# RFM12B_Breakout.net
KiCad netlist of a schematic drawn in EAGLE
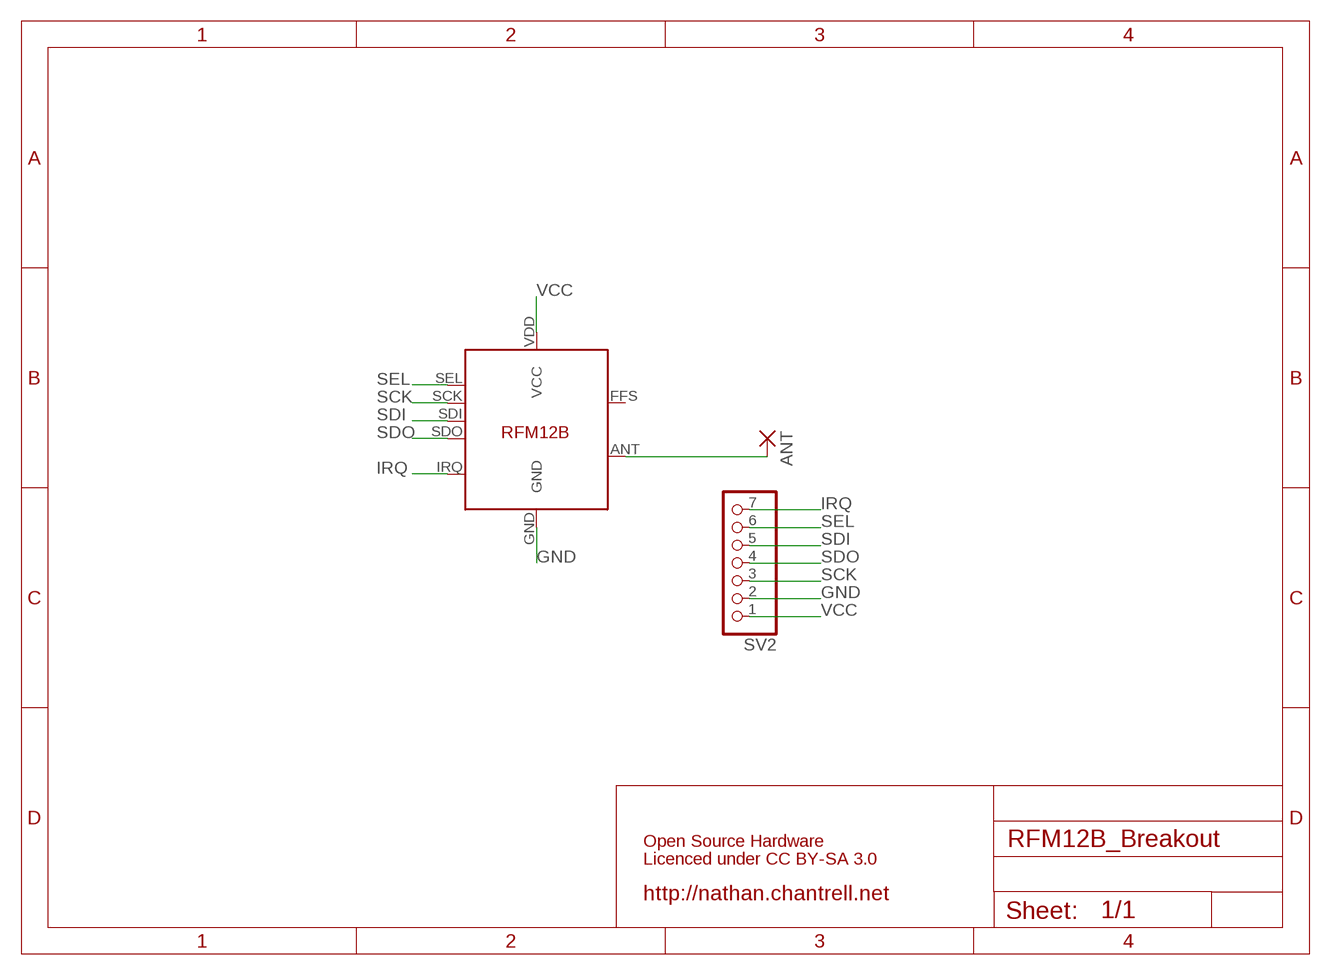
[diagram p0: schematic, sheet 1]

(export (version "E")
  (design (tool "Eeschema 10.0.6"))
  (components
    (comp (ref "ANT")
      (value "1,6/0,8")
      (footprint "eagle-import:1,6_0,8")
      (libsource (lib "eagle-import") (part "1,6/0,8"))
    )
    (comp (ref "SV2")
      (value "PINHD-1X7")
      (footprint "eagle-import:1X07")
      (libsource (lib "eagle-import") (part "PINHD-1X7"))
    )
    (comp (ref "U$1")
      (value "RFM12B")
      (footprint "eagle-import:RFM12B")
      (libsource (lib "eagle-import") (part "RFM12B"))
    )
  )
  (nets
    (net (code "1") (name "/GND") (class "Default")
      (node (ref "SV2") (pin "2") (pinfunction "2_2") (pintype "passive"))
      (node (ref "U$1") (pin "GND") (pinfunction "GND_GND") (pintype "power_in"))
    )
    (net (code "2") (name "/IRQ") (class "Default")
      (node (ref "SV2") (pin "7") (pinfunction "7_7") (pintype "passive"))
      (node (ref "U$1") (pin "IRQ") (pinfunction "IRQ_IRQ") (pintype "open_collector"))
    )
    (net (code "3") (name "/SCK") (class "Default")
      (node (ref "SV2") (pin "3") (pinfunction "3_3") (pintype "passive"))
      (node (ref "U$1") (pin "SCK") (pinfunction "SCK_SCK") (pintype "input"))
    )
    (net (code "4") (name "/SDI") (class "Default")
      (node (ref "SV2") (pin "5") (pinfunction "5_5") (pintype "passive"))
      (node (ref "U$1") (pin "SDI") (pinfunction "SDI_SDI") (pintype "input"))
    )
    (net (code "5") (name "/SDO") (class "Default")
      (node (ref "SV2") (pin "4") (pinfunction "4_4") (pintype "passive"))
      (node (ref "U$1") (pin "SDO") (pinfunction "SDO_SDO") (pintype "output"))
    )
    (net (code "6") (name "/SEL") (class "Default")
      (node (ref "SV2") (pin "6") (pinfunction "6_6") (pintype "passive"))
      (node (ref "U$1") (pin "SEL") (pinfunction "SEL_SEL") (pintype "input"))
    )
    (net (code "7") (name "/VCC") (class "Default")
      (node (ref "SV2") (pin "1") (pinfunction "1_1") (pintype "passive"))
      (node (ref "U$1") (pin "VDD") (pinfunction "VCC_VDD") (pintype "power_in"))
    )
    (net (code "8") (name "Net-(ANT-P)") (class "Default")
      (node (ref "ANT") (pin "1") (pinfunction "P_1") (pintype "passive"))
      (node (ref "U$1") (pin "ANT") (pinfunction "ANT_ANT") (pintype "passive"))
    )
    (net (code "9") (name "unconnected-(U$1-PadFFS)") (class "Default")
      (node (ref "U$1") (pin "FFS") (pinfunction "FFS_FFS") (pintype "bidirectional"))
    )
  )
)
